# 48V_Converter.net
KiCad netlist of a schematic drawn in Altium Designer
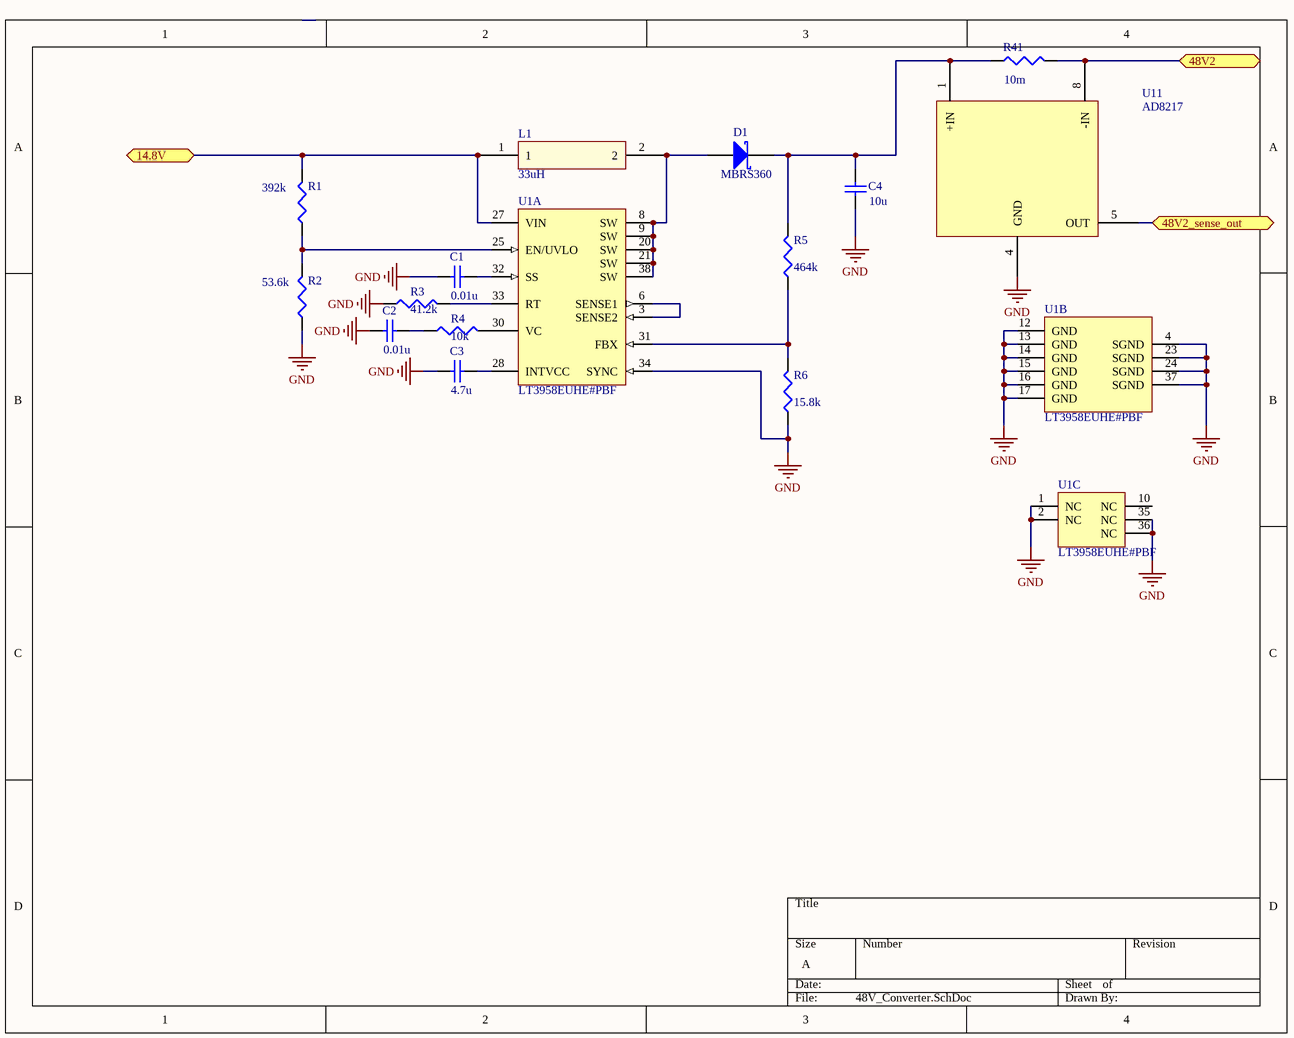
[diagram p0: 48V_Converter.SchDoc]

(export (version "E")
  (design (tool "Eeschema 10.0.6"))
  (components
    (comp (ref "C1")
      (value "0.01u")
      (footprint "C1206")
      (description "Capacitor (Semiconductor SIM Model)")
      (fields (field (name "Comment") "Cap Semi") (field (name "PUBLISHER") "Altium Limited"))
      (libsource (lib "Miscellaneous Devices") (part "Cap Semi"))
    )
    (comp (ref "C2")
      (value "0.01u")
      (footprint "C1206")
      (description "Capacitor (Semiconductor SIM Model)")
      (fields (field (name "Comment") "Cap Semi") (field (name "PUBLISHER") "Altium Limited"))
      (libsource (lib "Miscellaneous Devices") (part "Cap Semi"))
    )
    (comp (ref "C3")
      (value "4.7u")
      (footprint "C1206")
      (description "Capacitor (Semiconductor SIM Model)")
      (fields (field (name "Comment") "Cap Semi") (field (name "PUBLISHER") "Altium Limited"))
      (libsource (lib "Miscellaneous Devices") (part "Cap Semi"))
    )
    (comp (ref "C4")
      (value "10u")
      (footprint "C1206")
      (description "Capacitor (Semiconductor SIM Model)")
      (fields (field (name "Comment") "Cap Semi") (field (name "PUBLISHER") "Altium Limited"))
      (libsource (lib "Miscellaneous Devices") (part "Cap Semi"))
    )
    (comp (ref "D1")
      (value "MBRS360")
      (footprint "SMB")
      (description "Schottky Diode")
      (fields (field (name "PUBLISHER") "Altium Limited"))
      (libsource (lib "Miscellaneous Devices") (part "D Schottky"))
    )
    (comp (ref "L1")
      (value "33uH")
      (footprint "INDP125125X45N")
      (description "33uH Inductors")
      (libsource (lib "IHLP-6767DZ-11") (part "IHLP-6767DZ-11"))
    )
    (comp (ref "R1")
      (value "392k")
      (footprint "J1-0603")
      (description "Resistor")
      (fields (field (name "Comment") "Res3") (field (name "PUBLISHER") "Altium Limited"))
      (libsource (lib "Miscellaneous Devices") (part "Res3"))
    )
    (comp (ref "R2")
      (value "53.6k")
      (footprint "J1-0603")
      (description "Resistor")
      (fields (field (name "Comment") "Res3") (field (name "PUBLISHER") "Altium Limited"))
      (libsource (lib "Miscellaneous Devices") (part "Res3"))
    )
    (comp (ref "R3")
      (value "41.2k")
      (footprint "J1-0603")
      (description "Resistor")
      (fields (field (name "Comment") "Res3") (field (name "PUBLISHER") "Altium Limited"))
      (libsource (lib "Miscellaneous Devices") (part "Res3"))
    )
    (comp (ref "R4")
      (value "10k")
      (footprint "J1-0603")
      (description "Resistor")
      (fields (field (name "Comment") "Res3") (field (name "PUBLISHER") "Altium Limited"))
      (libsource (lib "Miscellaneous Devices") (part "Res3"))
    )
    (comp (ref "R5")
      (value "464k")
      (footprint "J1-0603")
      (description "Resistor")
      (fields (field (name "Comment") "Res3") (field (name "PUBLISHER") "Altium Limited"))
      (libsource (lib "Miscellaneous Devices") (part "Res3"))
    )
    (comp (ref "R6")
      (value "15.8k")
      (footprint "J1-0603")
      (description "Resistor")
      (fields (field (name "Comment") "Res3") (field (name "PUBLISHER") "Altium Limited"))
      (libsource (lib "Miscellaneous Devices") (part "Res3"))
    )
    (comp (ref "R41")
      (value "10m")
      (footprint "J1-0603")
      (description "Resistor")
      (fields (field (name "Comment") "Res3") (field (name "PUBLISHER") "Altium Limited"))
      (libsource (lib "Miscellaneous Devices") (part "Res3"))
    )
    (comp (ref "U1")
      (value "LT3958EUHE#PBF")
      (footprint "LT-UHE-36-V-UHE28MA_V")
      (fields (field (name "MANUFACTURER") "Linear Technology"))
      (libsource (lib "Linear Technology Power Management Switching Regulator LT1074-LT8705") (part "LT3958EUHE#PBF"))
    )
    (comp (ref "U11")
      (value "AD8217")
      (footprint "TSOP65P490X110-8N")
      (description "Current Shunt Moniter")
      (libsource (lib "AD8217") (part "Component_1"))
    )
  )
  (nets
    (net (code "1") (name "/14.8V") (class "Default")
      (node (ref "L1") (pin "1") (pinfunction "1_1") (pintype "passive"))
      (node (ref "R1") (pin "2") (pinfunction "2_2") (pintype "passive"))
      (node (ref "U1") (pin "27") (pinfunction "VIN_27") (pintype "power_in"))
    )
    (net (code "2") (name "/48V2") (class "Default")
      (node (ref "R41") (pin "2") (pinfunction "2_2") (pintype "passive"))
      (node (ref "U11") (pin "8") (pinfunction "-IN_8") (pintype "passive"))
    )
    (net (code "3") (name "/48V2_sense_out") (class "Default")
      (node (ref "U11") (pin "5") (pinfunction "OUT_5") (pintype "passive"))
    )
    (net (code "4") (name "GND") (class "Default")
      (node (ref "C1") (pin "1") (pinfunction "1_1") (pintype "passive"))
      (node (ref "C2") (pin "1") (pinfunction "1_1") (pintype "passive"))
      (node (ref "C3") (pin "1") (pinfunction "1_1") (pintype "passive"))
      (node (ref "C4") (pin "1") (pinfunction "1_1") (pintype "passive"))
      (node (ref "R2") (pin "1") (pinfunction "1_1") (pintype "passive"))
      (node (ref "R3") (pin "1") (pinfunction "1_1") (pintype "passive"))
      (node (ref "R6") (pin "1") (pinfunction "1_1") (pintype "passive"))
      (node (ref "U1") (pin "1") (pinfunction "NC_1") (pintype "passive"))
      (node (ref "U1") (pin "12") (pinfunction "GND_12") (pintype "power_in"))
      (node (ref "U1") (pin "13") (pinfunction "GND_13") (pintype "power_in"))
      (node (ref "U1") (pin "14") (pinfunction "GND_14") (pintype "power_in"))
      (node (ref "U1") (pin "15") (pinfunction "GND_15") (pintype "power_in"))
      (node (ref "U1") (pin "16") (pinfunction "GND_16") (pintype "power_in"))
      (node (ref "U1") (pin "17") (pinfunction "GND_17") (pintype "power_in"))
      (node (ref "U1") (pin "2") (pinfunction "NC_2") (pintype "passive"))
      (node (ref "U1") (pin "23") (pinfunction "SGND_23") (pintype "power_in"))
      (node (ref "U1") (pin "24") (pinfunction "SGND_24") (pintype "power_in"))
      (node (ref "U1") (pin "34") (pinfunction "SYNC_34") (pintype "input"))
      (node (ref "U1") (pin "35") (pinfunction "NC_35") (pintype "passive"))
      (node (ref "U1") (pin "36") (pinfunction "NC_36") (pintype "passive"))
      (node (ref "U1") (pin "37") (pinfunction "SGND_37") (pintype "power_in"))
      (node (ref "U1") (pin "4") (pinfunction "SGND_4") (pintype "power_in"))
      (node (ref "U11") (pin "4") (pinfunction "GND_4") (pintype "passive"))
    )
    (net (code "5") (name "Net-(C2-Pad2)") (class "Default")
      (node (ref "C2") (pin "2") (pinfunction "2_2") (pintype "passive"))
      (node (ref "R4") (pin "1") (pinfunction "1_1") (pintype "passive"))
    )
    (net (code "6") (name "Net-(D1-A)") (class "Default")
      (node (ref "D1") (pin "1") (pinfunction "A_1") (pintype "passive"))
      (node (ref "L1") (pin "2") (pinfunction "2_2") (pintype "passive"))
      (node (ref "U1") (pin "20") (pinfunction "SW_20") (pintype "power_in"))
      (node (ref "U1") (pin "21") (pinfunction "SW_21") (pintype "power_in"))
      (node (ref "U1") (pin "38") (pinfunction "SW_38") (pintype "power_in"))
      (node (ref "U1") (pin "8") (pinfunction "SW_8") (pintype "power_in"))
      (node (ref "U1") (pin "9") (pinfunction "SW_9") (pintype "power_in"))
    )
    (net (code "7") (name "Net-(D1-K)") (class "Default")
      (node (ref "C4") (pin "2") (pinfunction "2_2") (pintype "passive"))
      (node (ref "D1") (pin "2") (pinfunction "K_2") (pintype "passive"))
      (node (ref "R41") (pin "1") (pinfunction "1_1") (pintype "passive"))
      (node (ref "R5") (pin "2") (pinfunction "2_2") (pintype "passive"))
      (node (ref "U11") (pin "1") (pinfunction "+IN_1") (pintype "passive"))
    )
    (net (code "8") (name "Net-(U1A-EN{slash}UVLO)") (class "Default")
      (node (ref "R1") (pin "1") (pinfunction "1_1") (pintype "passive"))
      (node (ref "R2") (pin "2") (pinfunction "2_2") (pintype "passive"))
      (node (ref "U1") (pin "25") (pinfunction "EN/UVLO_25") (pintype "input"))
    )
    (net (code "9") (name "Net-(U1A-FBX)") (class "Default")
      (node (ref "R5") (pin "1") (pinfunction "1_1") (pintype "passive"))
      (node (ref "R6") (pin "2") (pinfunction "2_2") (pintype "passive"))
      (node (ref "U1") (pin "31") (pinfunction "FBX_31") (pintype "input"))
    )
    (net (code "10") (name "Net-(U1A-INTVCC)") (class "Default")
      (node (ref "C3") (pin "2") (pinfunction "2_2") (pintype "passive"))
      (node (ref "U1") (pin "28") (pinfunction "INTVCC_28") (pintype "power_in"))
    )
    (net (code "11") (name "Net-(U1A-RT)") (class "Default")
      (node (ref "R3") (pin "2") (pinfunction "2_2") (pintype "passive"))
      (node (ref "U1") (pin "33") (pinfunction "RT_33") (pintype "passive"))
    )
    (net (code "12") (name "Net-(U1A-SENSE1)") (class "Default")
      (node (ref "U1") (pin "3") (pinfunction "SENSE2_3") (pintype "input"))
      (node (ref "U1") (pin "6") (pinfunction "SENSE1_6") (pintype "output"))
    )
    (net (code "13") (name "Net-(U1A-SS)") (class "Default")
      (node (ref "C1") (pin "2") (pinfunction "2_2") (pintype "passive"))
      (node (ref "U1") (pin "32") (pinfunction "SS_32") (pintype "input"))
    )
    (net (code "14") (name "Net-(U1A-VC)") (class "Default")
      (node (ref "R4") (pin "2") (pinfunction "2_2") (pintype "passive"))
      (node (ref "U1") (pin "30") (pinfunction "VC_30") (pintype "passive"))
    )
    (net (code "15") (name "unconnected-(U1C-NC-Pad10)") (class "Default")
      (node (ref "U1") (pin "10") (pinfunction "NC_10") (pintype "passive"))
    )
  )
)
